# Mesure.net
KiCad netlist of a schematic drawn in Altium Designer
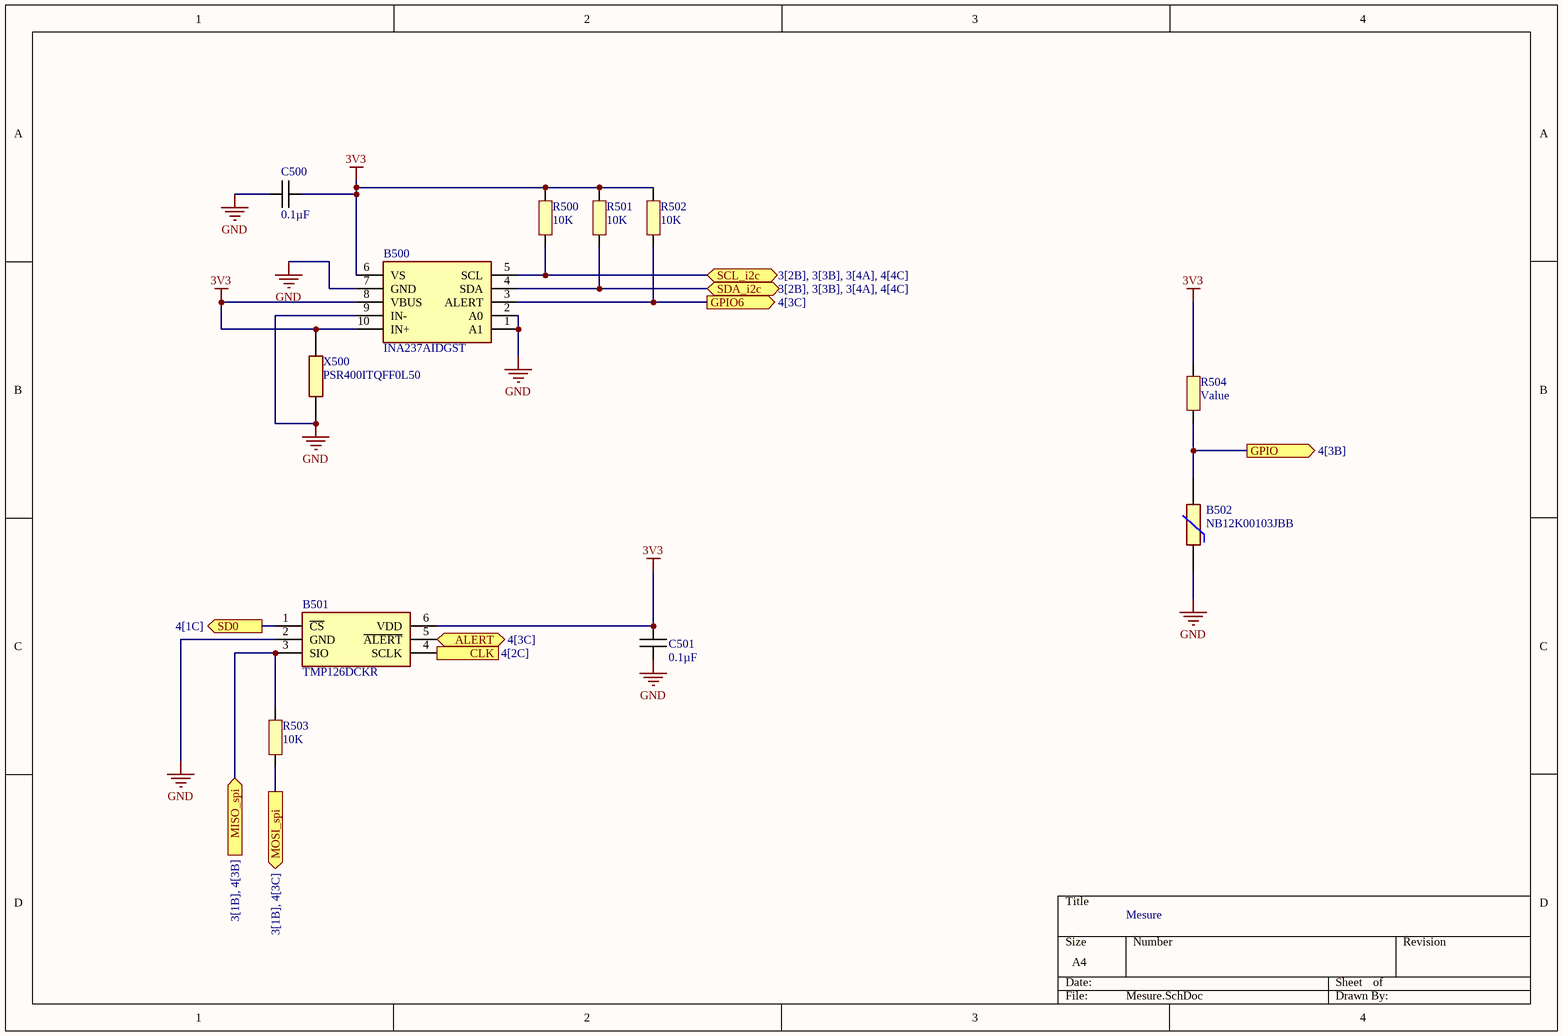
[diagram p0: Mesure.SchDoc]

(export (version "E")
  (design (tool "Eeschema 10.0.6"))
  (components
    (comp (ref "B500")
      (value "INA237AIDGST")
      (footprint "SOP50P490X110-10N")
      (fields (field (name "MOUSER PART NUMBER") "595-INA237AIDGST"))
      (libsource (lib "SCHLibrary") (part "INA237AIDGST"))
    )
    (comp (ref "B501")
      (value "TMP126DCKR")
      (footprint "SOT65P210X110-6N")
      (fields (field (name "MOUSER PART NUMBER") "595-TMP126DCKR"))
      (libsource (lib "SCHLibrary") (part "TMP126DCKR"))
    )
    (comp (ref "B502")
      (value "NB12K00103JBB")
      (footprint "RESC2212X50N")
      (description "NTC SMD Thermistor, NB12K, 10K, 5% AVX 10k 0805 Protection NTC Thermistor, 5s, 2 x 1.25 x 1.3mm")
      (fields (field (name "MOUSER PART NUMBER") "581-NB12K00103JBB"))
      (libsource (lib "SCHLibrary") (part "NB12K00103JBB"))
    )
    (comp (ref "C500")
      (value "0.1µF")
      (footprint "CAPC1005X06N")
      (libsource (lib "SCHLibrary") (part "Capacitor"))
    )
    (comp (ref "C501")
      (value "0.1µF")
      (footprint "CAPC1005X06N")
      (libsource (lib "SCHLibrary") (part "Capacitor"))
    )
    (comp (ref "R500")
      (value "10K")
      (footprint "RESC1005X06N")
      (libsource (lib "SCHLibrary") (part "Resistor"))
    )
    (comp (ref "R501")
      (value "10K")
      (footprint "RESC1005X06N")
      (libsource (lib "SCHLibrary") (part "Resistor"))
    )
    (comp (ref "R502")
      (value "10K")
      (footprint "RESC1005X06N")
      (libsource (lib "SCHLibrary") (part "Resistor"))
    )
    (comp (ref "R503") (value "10K") (footprint "RESC1005X06N") (libsource (lib "") (part "Resistor_1")))
    (comp (ref "R504") (value "Value") (footprint "RESC1005X06N") (libsource (lib "") (part "Resistor_1")))
    (comp (ref "X500")
      (value "PSR400ITQFF0L50")
      (footprint "RESC10052X200N")
      (fields (field (name "MOUSER PART NUMBER") "755-PSR400ITQFF0L50"))
      (libsource (lib "SCHLibrary") (part "PSR400ITQFF0L50"))
    )
  )
  (nets
    (net (code "1") (name "/ALERT") (class "Default")
      (node (ref "B501") (pin "5") (pinfunction "~{ALERT}_5") (pintype "passive"))
    )
    (net (code "2") (name "/CLK") (class "Default")
      (node (ref "B501") (pin "4") (pinfunction "SCLK_4") (pintype "passive"))
    )
    (net (code "3") (name "/GPIO") (class "Default")
      (node (ref "B502") (pin "2") (pinfunction "2_2") (pintype "passive"))
      (node (ref "R504") (pin "2") (pinfunction "2_2") (pintype "passive"))
    )
    (net (code "4") (name "/GPIO6") (class "Default")
      (node (ref "B500") (pin "3") (pinfunction "ALERT_3") (pintype "passive"))
      (node (ref "R502") (pin "1") (pinfunction "1_1") (pintype "passive"))
    )
    (net (code "5") (name "/MISO_spi") (class "Default")
      (node (ref "B501") (pin "3") (pinfunction "SIO_3") (pintype "passive"))
      (node (ref "R503") (pin "1") (pinfunction "1_1") (pintype "passive"))
    )
    (net (code "6") (name "/MOSI_spi") (class "Default")
      (node (ref "R503") (pin "2") (pinfunction "2_2") (pintype "passive"))
    )
    (net (code "7") (name "/SCL_i2c") (class "Default")
      (node (ref "B500") (pin "5") (pinfunction "SCL_5") (pintype "passive"))
      (node (ref "R500") (pin "1") (pinfunction "1_1") (pintype "passive"))
    )
    (net (code "8") (name "/SD0") (class "Default")
      (node (ref "B501") (pin "1") (pinfunction "~{CS}_1") (pintype "passive"))
    )
    (net (code "9") (name "/SDA_i2c") (class "Default")
      (node (ref "B500") (pin "4") (pinfunction "SDA_4") (pintype "passive"))
      (node (ref "R501") (pin "1") (pinfunction "1_1") (pintype "passive"))
    )
    (net (code "10") (name "3V3") (class "Default")
      (node (ref "B500") (pin "10") (pinfunction "IN+_10") (pintype "passive"))
      (node (ref "B500") (pin "6") (pinfunction "VS_6") (pintype "passive"))
      (node (ref "B500") (pin "8") (pinfunction "VBUS_8") (pintype "passive"))
      (node (ref "B501") (pin "6") (pinfunction "VDD_6") (pintype "passive"))
      (node (ref "C500") (pin "2") (pinfunction "2_2") (pintype "passive"))
      (node (ref "C501") (pin "2") (pinfunction "2_2") (pintype "passive"))
      (node (ref "R500") (pin "2") (pinfunction "2_2") (pintype "passive"))
      (node (ref "R501") (pin "2") (pinfunction "2_2") (pintype "passive"))
      (node (ref "R502") (pin "2") (pinfunction "2_2") (pintype "passive"))
      (node (ref "R504") (pin "1") (pinfunction "1_1") (pintype "passive"))
      (node (ref "X500") (pin "2") (pinfunction "2_2") (pintype "passive"))
    )
    (net (code "11") (name "GND") (class "Default")
      (node (ref "B500") (pin "1") (pinfunction "A1_1") (pintype "passive"))
      (node (ref "B500") (pin "2") (pinfunction "A0_2") (pintype "passive"))
      (node (ref "B500") (pin "7") (pinfunction "GND_7") (pintype "passive"))
      (node (ref "B500") (pin "9") (pinfunction "IN-_9") (pintype "passive"))
      (node (ref "B501") (pin "2") (pinfunction "GND_2") (pintype "passive"))
      (node (ref "B502") (pin "1") (pinfunction "1_1") (pintype "passive"))
      (node (ref "C500") (pin "1") (pinfunction "1_1") (pintype "passive"))
      (node (ref "C501") (pin "1") (pinfunction "1_1") (pintype "passive"))
      (node (ref "X500") (pin "1") (pinfunction "1_1") (pintype "passive"))
    )
  )
)
